# solo_cidlo.net
KiCad netlist of a schematic drawn in EAGLE
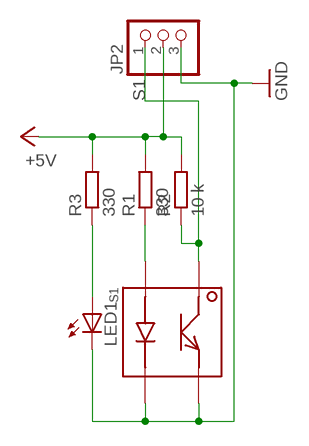
[diagram p0: schematic, sheet 1]

(export (version "E")
  (design (tool "Eeschema 10.0.6"))
  (components
    (comp (ref "JP2")
      (value "PINHD-1X3")
      (footprint "eagle-import:1X03")
      (libsource (lib "eagle-import") (part "PINHD-1X3"))
    )
    (comp (ref "LED1")
      (value "LEDCHIPLED_0603")
      (footprint "eagle-import:CHIPLED_0603")
      (libsource (lib "eagle-import") (part "LEDCHIPLED_0603"))
    )
    (comp (ref "R1")
      (value "330")
      (footprint "eagle-import:MINI_MELF-0102W")
      (libsource (lib "eagle-import") (part "R-EU_MELF0102W"))
    )
    (comp (ref "R2")
      (value "10 k")
      (footprint "eagle-import:MINI_MELF-0102W")
      (libsource (lib "eagle-import") (part "R-EU_MELF0102W"))
    )
    (comp (ref "R3")
      (value "330")
      (footprint "eagle-import:R0201")
      (libsource (lib "eagle-import") (part "R-EU_R0201"))
    )
    (comp (ref "S1")
      (value "QRD1114")
      (footprint "eagle-import:QRD1114")
      (fields (field (name "MF") "ON Semiconductor"))
      (libsource (lib "eagle-import") (part "QRD1114"))
    )
  )
  (nets
    (net (code "1") (name "+5V") (class "Default")
      (node (ref "JP2") (pin "2") (pinfunction "2_2") (pintype "passive"))
      (node (ref "R1") (pin "2") (pinfunction "2_2") (pintype "passive"))
      (node (ref "R2") (pin "2") (pinfunction "2_2") (pintype "passive"))
      (node (ref "R3") (pin "2") (pinfunction "2_2") (pintype "passive"))
    )
    (net (code "2") (name "/S1") (class "Default")
      (node (ref "JP2") (pin "1") (pinfunction "1_1") (pintype "passive"))
      (node (ref "R2") (pin "1") (pinfunction "1_1") (pintype "passive"))
      (node (ref "S1") (pin "P$1") (pinfunction "P$1_P$1") (pintype "bidirectional"))
    )
    (net (code "3") (name "GND") (class "Default")
      (node (ref "JP2") (pin "3") (pinfunction "3_3") (pintype "passive"))
      (node (ref "LED1") (pin "C") (pinfunction "C_C") (pintype "passive"))
      (node (ref "S1") (pin "P$2") (pinfunction "P$2_P$2") (pintype "bidirectional"))
      (node (ref "S1") (pin "P$4") (pinfunction "P$4_P$4") (pintype "bidirectional"))
    )
    (net (code "4") (name "Net-(LED1-PadA)") (class "Default")
      (node (ref "LED1") (pin "A") (pinfunction "A_A") (pintype "passive"))
      (node (ref "R3") (pin "1") (pinfunction "1_1") (pintype "passive"))
    )
    (net (code "5") (name "Net-(R1-Pad1)") (class "Default")
      (node (ref "R1") (pin "1") (pinfunction "1_1") (pintype "passive"))
      (node (ref "S1") (pin "P$3") (pinfunction "P$3_P$3") (pintype "bidirectional"))
    )
  )
)
